# schematic.net
KiCad netlist of a schematic drawn in EAGLE
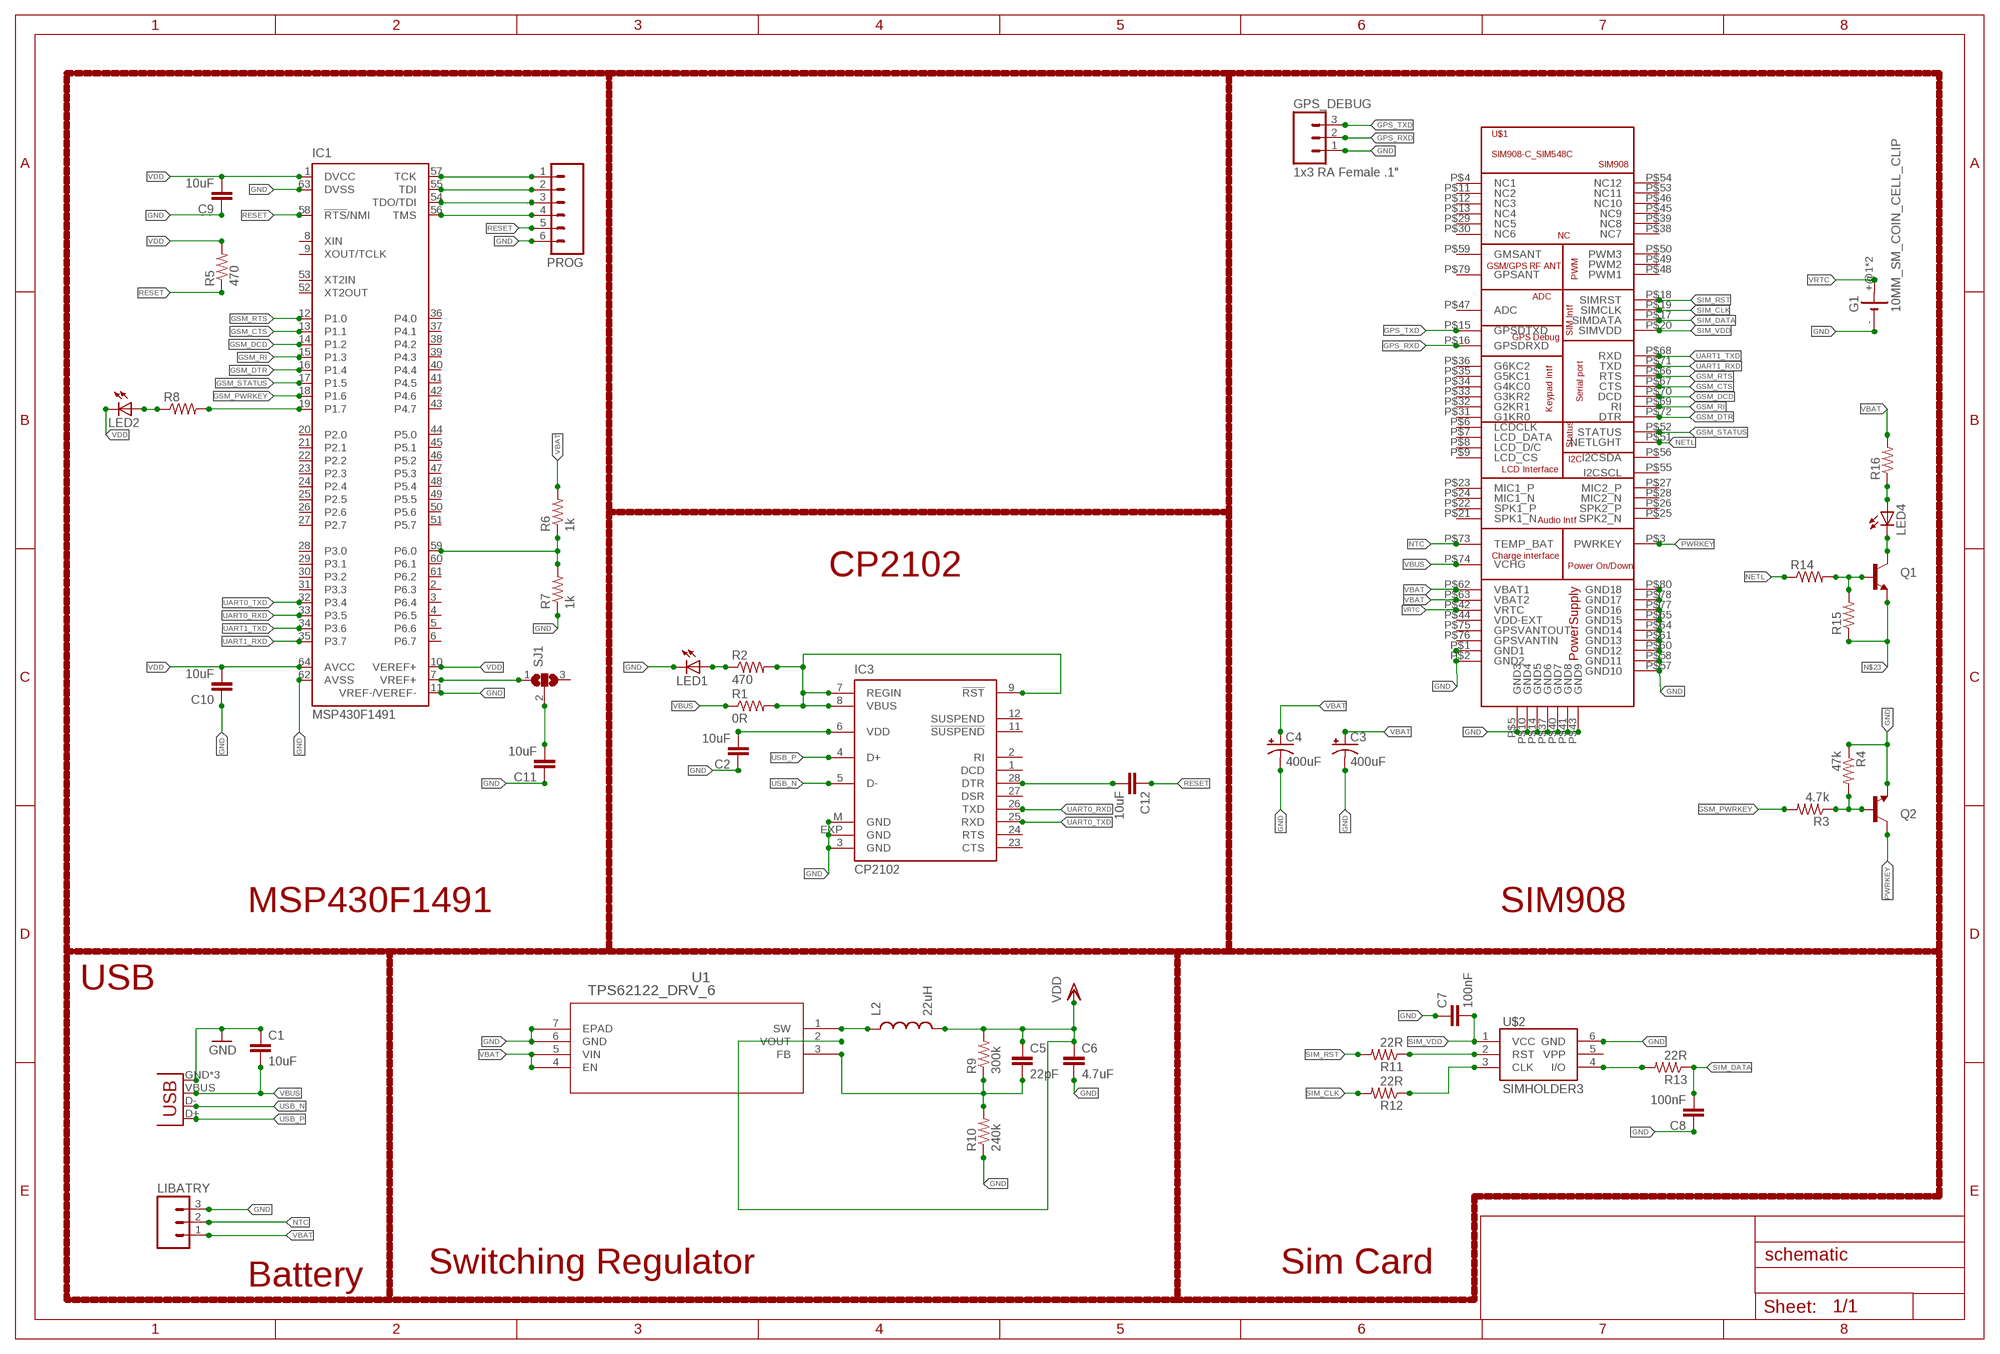
[diagram p0: schematic, sheet 1]

(export (version "E")
  (design (tool "Eeschema 10.0.6"))
  (components
    (comp (ref "C1")
      (value "10uF")
      (footprint "eagle-import:0402-CAP")
      (libsource (lib "eagle-import") (part "CAP0402-CAP"))
    )
    (comp (ref "C2")
      (value "10uF")
      (footprint "eagle-import:0402-CAP")
      (libsource (lib "eagle-import") (part "CAP0402-CAP"))
    )
    (comp (ref "C3")
      (value "400uF")
      (footprint "eagle-import:PANASONIC_G")
      (libsource (lib "eagle-import") (part "CAP_POLG"))
    )
    (comp (ref "C4")
      (value "400uF")
      (footprint "eagle-import:PANASONIC_G")
      (libsource (lib "eagle-import") (part "CAP_POLG"))
    )
    (comp (ref "C5")
      (value "22pF")
      (footprint "eagle-import:0402-CAP")
      (libsource (lib "eagle-import") (part "CAP0402-CAP"))
    )
    (comp (ref "C6")
      (value "4.7uF")
      (footprint "eagle-import:0402-CAP")
      (libsource (lib "eagle-import") (part "CAP0402-CAP"))
    )
    (comp (ref "C7")
      (value "100nF")
      (footprint "eagle-import:0402-CAP")
      (libsource (lib "eagle-import") (part "CAP0402-CAP"))
    )
    (comp (ref "C8")
      (value "100nF")
      (footprint "eagle-import:0402-CAP")
      (libsource (lib "eagle-import") (part "CAP0402-CAP"))
    )
    (comp (ref "C9")
      (value "10uF")
      (footprint "eagle-import:0402-CAP")
      (libsource (lib "eagle-import") (part "CAP0402-CAP"))
    )
    (comp (ref "C10")
      (value "10uF")
      (footprint "eagle-import:0402-CAP")
      (libsource (lib "eagle-import") (part "CAP0402-CAP"))
    )
    (comp (ref "C11")
      (value "10uF")
      (footprint "eagle-import:0402-CAP")
      (libsource (lib "eagle-import") (part "CAP0402-CAP"))
    )
    (comp (ref "C12")
      (value "10uF")
      (footprint "eagle-import:0402-CAP")
      (libsource (lib "eagle-import") (part "CAP0402-CAP"))
    )
    (comp (ref "G1")
      (value "10MM_SM_COIN_CELL_CLIP")
      (footprint "eagle-import:10MM_SM_COIN_CELL_CLIP")
      (libsource (lib "eagle-import") (part "10MM_SM_COIN_CELL_CLIP"))
    )
    (comp (ref "GPS_DEBUG")
      (value "1x3 RA Female .1\"")
      (footprint "eagle-import:1X03_SMD_RA_FEMALE")
      (libsource (lib "eagle-import") (part "M03SMD_RA_FEMALE"))
    )
    (comp (ref "IC1")
      (value "MSP430F1491")
      (footprint "eagle-import:SQFP-S-10X10-64")
      (fields (field (name "MF") "TEXAS INSTRUMENT CONNECTORS") (field (name "MPN") "MSP430F1491IPM"))
      (libsource (lib "eagle-import") (part "MSP430F1491"))
    )
    (comp (ref "IC3")
      (value "CP2102")
      (footprint "eagle-import:MLP28")
      (fields (field (name "MF") "FARNELL") (field (name "MPN") "CP2102-GM"))
      (libsource (lib "eagle-import") (part "CP2102"))
    )
    (comp (ref "JP1")
      (value "USB-MICROB")
      (footprint "eagle-import:USB-MICROB")
      (libsource (lib "eagle-import") (part "USB-MICROB"))
    )
    (comp (ref "L2")
      (value "22uH")
      (footprint "eagle-import:C0402")
      (libsource (lib "eagle-import") (part "INDUCTOR0402"))
    )
    (comp (ref "LED1")
      (value "LEDSML0603")
      (footprint "eagle-import:SML0603")
      (libsource (lib "eagle-import") (part "LEDSML0603"))
    )
    (comp (ref "LED2")
      (value "LEDSML0603")
      (footprint "eagle-import:SML0603")
      (libsource (lib "eagle-import") (part "LEDSML0603"))
    )
    (comp (ref "LED4")
      (value "LEDSML0603")
      (footprint "eagle-import:SML0603")
      (libsource (lib "eagle-import") (part "LEDSML0603"))
    )
    (comp (ref "LIBATRY")
      (value "M03PTH")
      (footprint "eagle-import:1X03")
      (libsource (lib "eagle-import") (part "M03PTH"))
    )
    (comp (ref "PROG")
      (value "M06SMD-STRAIGHT")
      (footprint "eagle-import:1X06_SMD_STRAIGHT")
      (libsource (lib "eagle-import") (part "M06SMD-STRAIGHT"))
    )
    (comp (ref "Q1")
      (value "TRANSISTOR_NPNSOT23")
      (footprint "eagle-import:SOT23")
      (libsource (lib "eagle-import") (part "TRANSISTOR_NPNSOT23"))
    )
    (comp (ref "Q2")
      (value "TRANSISTOR_NPNSOT23")
      (footprint "eagle-import:SOT23")
      (libsource (lib "eagle-import") (part "TRANSISTOR_NPNSOT23"))
    )
    (comp (ref "R1")
      (value "0R")
      (footprint "eagle-import:0402-RES")
      (libsource (lib "eagle-import") (part "SparkFun-Passives_RESISTOR0402-RES"))
    )
    (comp (ref "R2")
      (value "470")
      (footprint "eagle-import:0402-RES")
      (libsource (lib "eagle-import") (part "SparkFun-Passives_RESISTOR0402-RES"))
    )
    (comp (ref "R3")
      (value "4.7k")
      (footprint "eagle-import:0402-RES")
      (libsource (lib "eagle-import") (part "SparkFun-Passives_RESISTOR0402-RES"))
    )
    (comp (ref "R4")
      (value "47k")
      (footprint "eagle-import:0402-RES")
      (libsource (lib "eagle-import") (part "SparkFun-Passives_RESISTOR0402-RES"))
    )
    (comp (ref "R5")
      (value "470")
      (footprint "eagle-import:0402-RES")
      (libsource (lib "eagle-import") (part "SparkFun-Passives_RESISTOR0402-RES"))
    )
    (comp (ref "R6")
      (value "1k")
      (footprint "eagle-import:0402-RES")
      (libsource (lib "eagle-import") (part "SparkFun-Passives_RESISTOR0402-RES"))
    )
    (comp (ref "R7")
      (value "1k")
      (footprint "eagle-import:0402-RES")
      (libsource (lib "eagle-import") (part "SparkFun-Passives_RESISTOR0402-RES"))
    )
    (comp (ref "R8")
      (value "RESISTOR0402-RES")
      (footprint "eagle-import:0402-RES")
      (libsource (lib "eagle-import") (part "RESISTOR0402-RES"))
    )
    (comp (ref "R9")
      (value "300k")
      (footprint "eagle-import:0402-RES")
      (libsource (lib "eagle-import") (part "RESISTOR0402-RES"))
    )
    (comp (ref "R10")
      (value "240k")
      (footprint "eagle-import:0402-RES")
      (libsource (lib "eagle-import") (part "RESISTOR0402-RES"))
    )
    (comp (ref "R11")
      (value "22R")
      (footprint "eagle-import:0402-RES")
      (libsource (lib "eagle-import") (part "RESISTOR0402-RES"))
    )
    (comp (ref "R12")
      (value "22R")
      (footprint "eagle-import:0402-RES")
      (libsource (lib "eagle-import") (part "RESISTOR0402-RES"))
    )
    (comp (ref "R13")
      (value "22R")
      (footprint "eagle-import:0402-RES")
      (libsource (lib "eagle-import") (part "RESISTOR0402-RES"))
    )
    (comp (ref "R14")
      (value "RESISTOR0402-RES")
      (footprint "eagle-import:0402-RES")
      (libsource (lib "eagle-import") (part "SparkFun-Passives_RESISTOR0402-RES"))
    )
    (comp (ref "R15")
      (value "RESISTOR0402-RES")
      (footprint "eagle-import:0402-RES")
      (libsource (lib "eagle-import") (part "SparkFun-Passives_RESISTOR0402-RES"))
    )
    (comp (ref "R16")
      (value "RESISTOR0402-RES")
      (footprint "eagle-import:0402-RES")
      (libsource (lib "eagle-import") (part "RESISTOR0402-RES"))
    )
    (comp (ref "SJ1")
      (value "SJ2W")
      (footprint "eagle-import:SJ_2")
      (libsource (lib "eagle-import") (part "SJ2W"))
    )
    (comp (ref "U$1")
      (value "SIM908-C_SIM548C")
      (footprint "eagle-import:SIM908-C_SIM548C")
      (libsource (lib "eagle-import") (part "SIM908-C_SIM548C"))
    )
    (comp (ref "U$2")
      (value "SIMHOLDER3")
      (footprint "eagle-import:SIMHOLDER3")
      (libsource (lib "eagle-import") (part "SIMHOLDER3"))
    )
    (comp (ref "U1")
      (value "TPS62122_DRV_6")
      (footprint "eagle-import:DRV6_1P6X1")
      (fields
        (field (name "GENERIC_PART_NUMBER") "TPS62122")
        (field (name "MANUFACTURER") "Texas Instruments")
        (field (name "MANUFACTURER_PART_NUMBER") "tps62122_drv_6")
      )
      (libsource (lib "eagle-import") (part "TPS62122_DRV_6"))
    )
  )
  (nets
    (net (code "1") (name "GND") (class "Default")
      (node (ref "C1") (pin "1") (pinfunction "1_1") (pintype "passive"))
      (node (ref "C10") (pin "1") (pinfunction "1_1") (pintype "passive"))
      (node (ref "C11") (pin "1") (pinfunction "1_1") (pintype "passive"))
      (node (ref "C2") (pin "1") (pinfunction "1_1") (pintype "passive"))
      (node (ref "C3") (pin "-") (pinfunction "-_-") (pintype "passive"))
      (node (ref "C4") (pin "-") (pinfunction "-_-") (pintype "passive"))
      (node (ref "C6") (pin "2") (pinfunction "2_2") (pintype "passive"))
      (node (ref "C7") (pin "1") (pinfunction "1_1") (pintype "passive"))
      (node (ref "C8") (pin "1") (pinfunction "1_1") (pintype "passive"))
      (node (ref "C9") (pin "1") (pinfunction "1_1") (pintype "passive"))
      (node (ref "G1") (pin "-") (pinfunction "-_-") (pintype "passive"))
      (node (ref "GPS_DEBUG") (pin "1") (pinfunction "1_1") (pintype "passive"))
      (node (ref "IC1") (pin "11") (pinfunction "VREF-/VEREF-_11") (pintype "bidirectional"))
      (node (ref "IC1") (pin "62") (pinfunction "AVSS_62") (pintype "power_in"))
      (node (ref "IC1") (pin "63") (pinfunction "DVSS_63") (pintype "power_in"))
      (node (ref "IC3") (pin "3") (pinfunction "GND_3") (pintype "power_in"))
      (node (ref "IC3") (pin "EXP") (pinfunction "GND_EXP") (pintype "power_in"))
      (node (ref "IC3") (pin "M") (pinfunction "GND_M") (pintype "power_in"))
      (node (ref "JP1") (pin "GND") (pinfunction "GND_GND") (pintype "bidirectional"))
      (node (ref "JP1") (pin "MT1") (pinfunction "GND_MT1") (pintype "bidirectional"))
      (node (ref "JP1") (pin "MT2") (pinfunction "GND_MT2") (pintype "bidirectional"))
      (node (ref "LED1") (pin "C") (pinfunction "C_C") (pintype "passive"))
      (node (ref "LIBATRY") (pin "3") (pinfunction "3_3") (pintype "passive"))
      (node (ref "PROG") (pin "6") (pinfunction "6_6") (pintype "passive"))
      (node (ref "Q2") (pin "2") (pinfunction "E_2") (pintype "passive"))
      (node (ref "R10") (pin "1") (pinfunction "1_1") (pintype "passive"))
      (node (ref "R4") (pin "1") (pinfunction "1_1") (pintype "passive"))
      (node (ref "R7") (pin "1") (pinfunction "1_1") (pintype "passive"))
      (node (ref "U$1") (pin "P$1") (pinfunction "GND1_P$1") (pintype "bidirectional"))
      (node (ref "U$1") (pin "P$10") (pinfunction "GND4_P$10") (pintype "bidirectional"))
      (node (ref "U$1") (pin "P$14") (pinfunction "GND5_P$14") (pintype "bidirectional"))
      (node (ref "U$1") (pin "P$2") (pinfunction "GND2_P$2") (pintype "bidirectional"))
      (node (ref "U$1") (pin "P$37") (pinfunction "GND6_P$37") (pintype "bidirectional"))
      (node (ref "U$1") (pin "P$40") (pinfunction "GND7_P$40") (pintype "bidirectional"))
      (node (ref "U$1") (pin "P$41") (pinfunction "GND8_P$41") (pintype "bidirectional"))
      (node (ref "U$1") (pin "P$43") (pinfunction "GND9_P$43") (pintype "bidirectional"))
      (node (ref "U$1") (pin "P$5") (pinfunction "GND3_P$5") (pintype "bidirectional"))
      (node (ref "U$1") (pin "P$57") (pinfunction "GND10_P$57") (pintype "bidirectional"))
      (node (ref "U$1") (pin "P$58") (pinfunction "GND11_P$58") (pintype "bidirectional"))
      (node (ref "U$1") (pin "P$60") (pinfunction "GND12_P$60") (pintype "bidirectional"))
      (node (ref "U$1") (pin "P$61") (pinfunction "GND13_P$61") (pintype "bidirectional"))
      (node (ref "U$1") (pin "P$64") (pinfunction "GND14_P$64") (pintype "bidirectional"))
      (node (ref "U$1") (pin "P$65") (pinfunction "GND15_P$65") (pintype "bidirectional"))
      (node (ref "U$1") (pin "P$77") (pinfunction "GND16_P$77") (pintype "bidirectional"))
      (node (ref "U$1") (pin "P$78") (pinfunction "GND17_P$78") (pintype "bidirectional"))
      (node (ref "U$1") (pin "P$80") (pinfunction "GND18_P$80") (pintype "bidirectional"))
      (node (ref "U$2") (pin "6") (pinfunction "GND_6") (pintype "bidirectional"))
      (node (ref "U1") (pin "6") (pinfunction "GND_6") (pintype "power_in"))
      (node (ref "U1") (pin "7") (pinfunction "EPAD_7") (pintype "passive"))
    )
    (net (code "2") (name "GPS_RXD") (class "Default")
      (node (ref "GPS_DEBUG") (pin "2") (pinfunction "2_2") (pintype "passive"))
      (node (ref "U$1") (pin "P$16") (pinfunction "GPSDRXD_P$16") (pintype "bidirectional"))
    )
    (net (code "3") (name "GPS_TXD") (class "Default")
      (node (ref "GPS_DEBUG") (pin "3") (pinfunction "3_3") (pintype "passive"))
      (node (ref "U$1") (pin "P$15") (pinfunction "GPSDTXD_P$15") (pintype "bidirectional"))
    )
    (net (code "4") (name "GSM_CTS") (class "Default")
      (node (ref "IC1") (pin "13") (pinfunction "P1.1_13") (pintype "bidirectional"))
      (node (ref "U$1") (pin "P$67") (pinfunction "CTS_P$67") (pintype "bidirectional"))
    )
    (net (code "5") (name "GSM_DCD") (class "Default")
      (node (ref "IC1") (pin "14") (pinfunction "P1.2_14") (pintype "bidirectional"))
      (node (ref "U$1") (pin "P$70") (pinfunction "DCD_P$70") (pintype "bidirectional"))
    )
    (net (code "6") (name "GSM_DTR") (class "Default")
      (node (ref "IC1") (pin "16") (pinfunction "P1.4_16") (pintype "bidirectional"))
      (node (ref "U$1") (pin "P$72") (pinfunction "DTR_P$72") (pintype "bidirectional"))
    )
    (net (code "7") (name "GSM_PWRKEY") (class "Default")
      (node (ref "IC1") (pin "18") (pinfunction "P1.6_18") (pintype "bidirectional"))
      (node (ref "R3") (pin "2") (pinfunction "2_2") (pintype "passive"))
    )
    (net (code "8") (name "GSM_RI") (class "Default")
      (node (ref "IC1") (pin "15") (pinfunction "P1.3_15") (pintype "bidirectional"))
      (node (ref "U$1") (pin "P$69") (pinfunction "RI_P$69") (pintype "bidirectional"))
    )
    (net (code "9") (name "GSM_RTS") (class "Default")
      (node (ref "IC1") (pin "12") (pinfunction "P1.0_12") (pintype "bidirectional"))
      (node (ref "U$1") (pin "P$66") (pinfunction "RTS_P$66") (pintype "bidirectional"))
    )
    (net (code "10") (name "GSM_STATUS") (class "Default")
      (node (ref "IC1") (pin "17") (pinfunction "P1.5_17") (pintype "bidirectional"))
      (node (ref "U$1") (pin "P$52") (pinfunction "STATUS_P$52") (pintype "bidirectional"))
    )
    (net (code "11") (name "N$23") (class "Default")
      (node (ref "Q1") (pin "2") (pinfunction "E_2") (pintype "passive"))
      (node (ref "R15") (pin "1") (pinfunction "1_1") (pintype "passive"))
    )
    (net (code "12") (name "NETL") (class "Default")
      (node (ref "R14") (pin "1") (pinfunction "1_1") (pintype "passive"))
      (node (ref "U$1") (pin "P$51") (pinfunction "NETLGHT_P$51") (pintype "bidirectional"))
    )
    (net (code "13") (name "NTC") (class "Default")
      (node (ref "LIBATRY") (pin "2") (pinfunction "2_2") (pintype "passive"))
      (node (ref "U$1") (pin "P$73") (pinfunction "TEMP_BAT_P$73") (pintype "bidirectional"))
    )
    (net (code "14") (name "Net-(C11-Pad2)") (class "Default")
      (node (ref "C11") (pin "2") (pinfunction "2_2") (pintype "passive"))
      (node (ref "SJ1") (pin "2") (pinfunction "2_2") (pintype "passive"))
    )
    (net (code "15") (name "Net-(IC1-P1.7)") (class "Default")
      (node (ref "IC1") (pin "19") (pinfunction "P1.7_19") (pintype "bidirectional"))
      (node (ref "R8") (pin "2") (pinfunction "2_2") (pintype "passive"))
    )
    (net (code "16") (name "Net-(IC1-P6.0)") (class "Default")
      (node (ref "IC1") (pin "59") (pinfunction "P6.0_59") (pintype "bidirectional"))
      (node (ref "R6") (pin "1") (pinfunction "1_1") (pintype "passive"))
      (node (ref "R7") (pin "2") (pinfunction "2_2") (pintype "passive"))
    )
    (net (code "17") (name "Net-(IC1-TCK)") (class "Default")
      (node (ref "IC1") (pin "57") (pinfunction "TCK_57") (pintype "input"))
      (node (ref "PROG") (pin "1") (pinfunction "1_1") (pintype "passive"))
    )
    (net (code "18") (name "Net-(IC1-TDI)") (class "Default")
      (node (ref "IC1") (pin "55") (pinfunction "TDI_55") (pintype "input"))
      (node (ref "PROG") (pin "2") (pinfunction "2_2") (pintype "passive"))
    )
    (net (code "19") (name "Net-(IC1-TDO{slash}TDI)") (class "Default")
      (node (ref "IC1") (pin "54") (pinfunction "TDO/TDI_54") (pintype "bidirectional"))
      (node (ref "PROG") (pin "3") (pinfunction "3_3") (pintype "passive"))
    )
    (net (code "20") (name "Net-(IC1-TMS)") (class "Default")
      (node (ref "IC1") (pin "56") (pinfunction "TMS_56") (pintype "input"))
      (node (ref "PROG") (pin "4") (pinfunction "4_4") (pintype "passive"))
    )
    (net (code "21") (name "Net-(IC1-VREF+)") (class "Default")
      (node (ref "IC1") (pin "7") (pinfunction "VREF+_7") (pintype "output"))
      (node (ref "SJ1") (pin "1") (pinfunction "1_1") (pintype "passive"))
    )
    (net (code "22") (name "Net-(IC3-DTR)") (class "Default")
      (node (ref "C12") (pin "2") (pinfunction "2_2") (pintype "passive"))
      (node (ref "IC3") (pin "28") (pinfunction "DTR_28") (pintype "output"))
    )
    (net (code "23") (name "Net-(IC3-REGIN)") (class "Default")
      (node (ref "IC3") (pin "7") (pinfunction "REGIN_7") (pintype "passive"))
      (node (ref "IC3") (pin "8") (pinfunction "VBUS_8") (pintype "input"))
      (node (ref "IC3") (pin "9") (pinfunction "~{RST}_9") (pintype "bidirectional"))
      (node (ref "R1") (pin "2") (pinfunction "2_2") (pintype "passive"))
      (node (ref "R2") (pin "2") (pinfunction "2_2") (pintype "passive"))
    )
    (net (code "24") (name "Net-(IC3-VDD)") (class "Default")
      (node (ref "C2") (pin "2") (pinfunction "2_2") (pintype "passive"))
      (node (ref "IC3") (pin "6") (pinfunction "VDD_6") (pintype "power_in"))
    )
    (net (code "25") (name "Net-(LED1-PadA)") (class "Default")
      (node (ref "LED1") (pin "A") (pinfunction "A_A") (pintype "passive"))
      (node (ref "R2") (pin "1") (pinfunction "1_1") (pintype "passive"))
    )
    (net (code "26") (name "Net-(LED2-PadA)") (class "Default")
      (node (ref "LED2") (pin "A") (pinfunction "A_A") (pintype "passive"))
      (node (ref "R8") (pin "1") (pinfunction "1_1") (pintype "passive"))
    )
    (net (code "27") (name "Net-(LED4-PadA)") (class "Default")
      (node (ref "LED4") (pin "A") (pinfunction "A_A") (pintype "passive"))
      (node (ref "R16") (pin "1") (pinfunction "1_1") (pintype "passive"))
    )
    (net (code "28") (name "Net-(Q1-B)") (class "Default")
      (node (ref "Q1") (pin "1") (pinfunction "B_1") (pintype "passive"))
      (node (ref "R14") (pin "2") (pinfunction "2_2") (pintype "passive"))
      (node (ref "R15") (pin "2") (pinfunction "2_2") (pintype "passive"))
    )
    (net (code "29") (name "Net-(Q1-C)") (class "Default")
      (node (ref "LED4") (pin "C") (pinfunction "C_C") (pintype "passive"))
      (node (ref "Q1") (pin "3") (pinfunction "C_3") (pintype "passive"))
    )
    (net (code "30") (name "Net-(Q2-B)") (class "Default")
      (node (ref "Q2") (pin "1") (pinfunction "B_1") (pintype "passive"))
      (node (ref "R3") (pin "1") (pinfunction "1_1") (pintype "passive"))
      (node (ref "R4") (pin "2") (pinfunction "2_2") (pintype "passive"))
    )
    (net (code "31") (name "Net-(U$2-CLK)") (class "Default")
      (node (ref "R12") (pin "1") (pinfunction "1_1") (pintype "passive"))
      (node (ref "U$2") (pin "3") (pinfunction "CLK_3") (pintype "bidirectional"))
    )
    (net (code "32") (name "Net-(U$2-I{slash}O)") (class "Default")
      (node (ref "R13") (pin "2") (pinfunction "2_2") (pintype "passive"))
      (node (ref "U$2") (pin "4") (pinfunction "I/O_4") (pintype "bidirectional"))
    )
    (net (code "33") (name "Net-(U$2-RST)") (class "Default")
      (node (ref "R11") (pin "1") (pinfunction "1_1") (pintype "passive"))
      (node (ref "U$2") (pin "2") (pinfunction "RST_2") (pintype "bidirectional"))
    )
    (net (code "34") (name "Net-(U1-FB)") (class "Default")
      (node (ref "C5") (pin "2") (pinfunction "2_2") (pintype "passive"))
      (node (ref "R10") (pin "2") (pinfunction "2_2") (pintype "passive"))
      (node (ref "R9") (pin "1") (pinfunction "1_1") (pintype "passive"))
      (node (ref "U1") (pin "3") (pinfunction "FB_3") (pintype "input"))
    )
    (net (code "35") (name "Net-(U1-SW)") (class "Default")
      (node (ref "L2") (pin "1") (pinfunction "1_1") (pintype "passive"))
      (node (ref "U1") (pin "1") (pinfunction "SW_1") (pintype "output"))
    )
    (net (code "36") (name "PWRKEY") (class "Default")
      (node (ref "Q2") (pin "3") (pinfunction "C_3") (pintype "passive"))
      (node (ref "U$1") (pin "P$3") (pinfunction "PWRKEY_P$3") (pintype "bidirectional"))
    )
    (net (code "37") (name "RESET") (class "Default")
      (node (ref "C12") (pin "1") (pinfunction "1_1") (pintype "passive"))
      (node (ref "IC1") (pin "58") (pinfunction "~{RTS}/NMI_58") (pintype "input"))
      (node (ref "PROG") (pin "5") (pinfunction "5_5") (pintype "passive"))
      (node (ref "R5") (pin "1") (pinfunction "1_1") (pintype "passive"))
    )
    (net (code "38") (name "SIM_CLK") (class "Default")
      (node (ref "R12") (pin "2") (pinfunction "2_2") (pintype "passive"))
      (node (ref "U$1") (pin "P$19") (pinfunction "SIMCLK_P$19") (pintype "bidirectional"))
    )
    (net (code "39") (name "SIM_DATA") (class "Default")
      (node (ref "C8") (pin "2") (pinfunction "2_2") (pintype "passive"))
      (node (ref "R13") (pin "1") (pinfunction "1_1") (pintype "passive"))
      (node (ref "U$1") (pin "P$17") (pinfunction "SIMDATA_P$17") (pintype "bidirectional"))
    )
    (net (code "40") (name "SIM_RST") (class "Default")
      (node (ref "R11") (pin "2") (pinfunction "2_2") (pintype "passive"))
      (node (ref "U$1") (pin "P$18") (pinfunction "SIMRST_P$18") (pintype "bidirectional"))
    )
    (net (code "41") (name "SIM_VDD") (class "Default")
      (node (ref "C7") (pin "2") (pinfunction "2_2") (pintype "passive"))
      (node (ref "U$1") (pin "P$20") (pinfunction "SIMVDD_P$20") (pintype "bidirectional"))
      (node (ref "U$2") (pin "1") (pinfunction "VCC_1") (pintype "bidirectional"))
    )
    (net (code "42") (name "UART0_RXD") (class "Default")
      (node (ref "IC1") (pin "33") (pinfunction "P3.5_33") (pintype "bidirectional"))
      (node (ref "IC3") (pin "26") (pinfunction "TXD_26") (pintype "output"))
    )
    (net (code "43") (name "UART0_TXD") (class "Default")
      (node (ref "IC1") (pin "32") (pinfunction "P3.4_32") (pintype "bidirectional"))
      (node (ref "IC3") (pin "25") (pinfunction "RXD_25") (pintype "input"))
    )
    (net (code "44") (name "UART1_RXD") (class "Default")
      (node (ref "IC1") (pin "35") (pinfunction "P3.7_35") (pintype "bidirectional"))
      (node (ref "U$1") (pin "P$71") (pinfunction "TXD_P$71") (pintype "bidirectional"))
    )
    (net (code "45") (name "UART1_TXD") (class "Default")
      (node (ref "IC1") (pin "34") (pinfunction "P3.6_34") (pintype "bidirectional"))
      (node (ref "U$1") (pin "P$68") (pinfunction "RXD_P$68") (pintype "bidirectional"))
    )
    (net (code "46") (name "USB_N") (class "Default")
      (node (ref "IC3") (pin "5") (pinfunction "D-_5") (pintype "bidirectional"))
      (node (ref "JP1") (pin "D-") (pinfunction "D-_D-") (pintype "bidirectional"))
    )
    (net (code "47") (name "USB_P") (class "Default")
      (node (ref "IC3") (pin "4") (pinfunction "D+_4") (pintype "bidirectional"))
      (node (ref "JP1") (pin "D+") (pinfunction "D+_D+") (pintype "bidirectional"))
    )
    (net (code "48") (name "VBAT") (class "Default")
      (node (ref "C3") (pin "+") (pinfunction "+_+") (pintype "passive"))
      (node (ref "C4") (pin "+") (pinfunction "+_+") (pintype "passive"))
      (node (ref "LIBATRY") (pin "1") (pinfunction "1_1") (pintype "passive"))
      (node (ref "R16") (pin "2") (pinfunction "2_2") (pintype "passive"))
      (node (ref "R6") (pin "2") (pinfunction "2_2") (pintype "passive"))
      (node (ref "U$1") (pin "P$62") (pinfunction "VBAT1_P$62") (pintype "bidirectional"))
      (node (ref "U$1") (pin "P$63") (pinfunction "VBAT2_P$63") (pintype "bidirectional"))
      (node (ref "U1") (pin "4") (pinfunction "EN_4") (pintype "input"))
      (node (ref "U1") (pin "5") (pinfunction "VIN_5") (pintype "power_in"))
    )
    (net (code "49") (name "VBUS") (class "Default")
      (node (ref "C1") (pin "2") (pinfunction "2_2") (pintype "passive"))
      (node (ref "JP1") (pin "VBUS") (pinfunction "VBUS_VBUS") (pintype "bidirectional"))
      (node (ref "R1") (pin "1") (pinfunction "1_1") (pintype "passive"))
      (node (ref "U$1") (pin "P$74") (pinfunction "VCHG_P$74") (pintype "bidirectional"))
    )
    (net (code "50") (name "VDD") (class "Default")
      (node (ref "C10") (pin "2") (pinfunction "2_2") (pintype "passive"))
      (node (ref "C5") (pin "1") (pinfunction "1_1") (pintype "passive"))
      (node (ref "C6") (pin "1") (pinfunction "1_1") (pintype "passive"))
      (node (ref "C9") (pin "2") (pinfunction "2_2") (pintype "passive"))
      (node (ref "IC1") (pin "1") (pinfunction "DVCC_1") (pintype "power_in"))
      (node (ref "IC1") (pin "10") (pinfunction "VEREF+_10") (pintype "input"))
      (node (ref "IC1") (pin "64") (pinfunction "AVCC_64") (pintype "power_in"))
      (node (ref "L2") (pin "2") (pinfunction "2_2") (pintype "passive"))
      (node (ref "LED2") (pin "C") (pinfunction "C_C") (pintype "passive"))
      (node (ref "R5") (pin "2") (pinfunction "2_2") (pintype "passive"))
      (node (ref "R9") (pin "2") (pinfunction "2_2") (pintype "passive"))
      (node (ref "U1") (pin "2") (pinfunction "VOUT_2") (pintype "input"))
    )
    (net (code "51") (name "VRTC") (class "Default")
      (node (ref "G1") (pin "+@1") (pinfunction "+_+@1") (pintype "passive"))
      (node (ref "G1") (pin "+@2") (pinfunction "+_+@2") (pintype "passive"))
      (node (ref "U$1") (pin "P$42") (pinfunction "VRTC_P$42") (pintype "bidirectional"))
    )
    (net (code "52") (name "unconnected-(IC1-P2.0-Pad20)") (class "Default")
      (node (ref "IC1") (pin "20") (pinfunction "P2.0_20") (pintype "bidirectional"))
    )
    (net (code "53") (name "unconnected-(IC1-P2.1-Pad21)") (class "Default")
      (node (ref "IC1") (pin "21") (pinfunction "P2.1_21") (pintype "bidirectional"))
    )
    (net (code "54") (name "unconnected-(IC1-P2.2-Pad22)") (class "Default")
      (node (ref "IC1") (pin "22") (pinfunction "P2.2_22") (pintype "bidirectional"))
    )
    (net (code "55") (name "unconnected-(IC1-P2.3-Pad23)") (class "Default")
      (node (ref "IC1") (pin "23") (pinfunction "P2.3_23") (pintype "bidirectional"))
    )
    (net (code "56") (name "unconnected-(IC1-P2.4-Pad24)") (class "Default")
      (node (ref "IC1") (pin "24") (pinfunction "P2.4_24") (pintype "bidirectional"))
    )
    (net (code "57") (name "unconnected-(IC1-P2.5-Pad25)") (class "Default")
      (node (ref "IC1") (pin "25") (pinfunction "P2.5_25") (pintype "bidirectional"))
    )
    (net (code "58") (name "unconnected-(IC1-P2.6-Pad26)") (class "Default")
      (node (ref "IC1") (pin "26") (pinfunction "P2.6_26") (pintype "bidirectional"))
    )
    (net (code "59") (name "unconnected-(IC1-P2.7-Pad27)") (class "Default")
      (node (ref "IC1") (pin "27") (pinfunction "P2.7_27") (pintype "bidirectional"))
    )
    (net (code "60") (name "unconnected-(IC1-P3.0-Pad28)") (class "Default")
      (node (ref "IC1") (pin "28") (pinfunction "P3.0_28") (pintype "bidirectional"))
    )
    (net (code "61") (name "unconnected-(IC1-P3.1-Pad29)") (class "Default")
      (node (ref "IC1") (pin "29") (pinfunction "P3.1_29") (pintype "bidirectional"))
    )
    (net (code "62") (name "unconnected-(IC1-P3.2-Pad30)") (class "Default")
      (node (ref "IC1") (pin "30") (pinfunction "P3.2_30") (pintype "bidirectional"))
    )
    (net (code "63") (name "unconnected-(IC1-P3.3-Pad31)") (class "Default")
      (node (ref "IC1") (pin "31") (pinfunction "P3.3_31") (pintype "bidirectional"))
    )
    (net (code "64") (name "unconnected-(IC1-P4.0-Pad36)") (class "Default")
      (node (ref "IC1") (pin "36") (pinfunction "P4.0_36") (pintype "bidirectional"))
    )
    (net (code "65") (name "unconnected-(IC1-P4.1-Pad37)") (class "Default")
      (node (ref "IC1") (pin "37") (pinfunction "P4.1_37") (pintype "bidirectional"))
    )
    (net (code "66") (name "unconnected-(IC1-P4.2-Pad38)") (class "Default")
      (node (ref "IC1") (pin "38") (pinfunction "P4.2_38") (pintype "bidirectional"))
    )
    (net (code "67") (name "unconnected-(IC1-P4.3-Pad39)") (class "Default")
      (node (ref "IC1") (pin "39") (pinfunction "P4.3_39") (pintype "bidirectional"))
    )
    (net (code "68") (name "unconnected-(IC1-P4.4-Pad40)") (class "Default")
      (node (ref "IC1") (pin "40") (pinfunction "P4.4_40") (pintype "bidirectional"))
    )
    (net (code "69") (name "unconnected-(IC1-P4.5-Pad41)") (class "Default")
      (node (ref "IC1") (pin "41") (pinfunction "P4.5_41") (pintype "bidirectional"))
    )
    (net (code "70") (name "unconnected-(IC1-P4.6-Pad42)") (class "Default")
      (node (ref "IC1") (pin "42") (pinfunction "P4.6_42") (pintype "bidirectional"))
    )
    (net (code "71") (name "unconnected-(IC1-P4.7-Pad43)") (class "Default")
      (node (ref "IC1") (pin "43") (pinfunction "P4.7_43") (pintype "bidirectional"))
    )
    (net (code "72") (name "unconnected-(IC1-P5.0-Pad44)") (class "Default")
      (node (ref "IC1") (pin "44") (pinfunction "P5.0_44") (pintype "bidirectional"))
    )
    (net (code "73") (name "unconnected-(IC1-P5.1-Pad45)") (class "Default")
      (node (ref "IC1") (pin "45") (pinfunction "P5.1_45") (pintype "bidirectional"))
    )
    (net (code "74") (name "unconnected-(IC1-P5.2-Pad46)") (class "Default")
      (node (ref "IC1") (pin "46") (pinfunction "P5.2_46") (pintype "bidirectional"))
    )
    (net (code "75") (name "unconnected-(IC1-P5.3-Pad47)") (class "Default")
      (node (ref "IC1") (pin "47") (pinfunction "P5.3_47") (pintype "bidirectional"))
    )
    (net (code "76") (name "unconnected-(IC1-P5.4-Pad48)") (class "Default")
      (node (ref "IC1") (pin "48") (pinfunction "P5.4_48") (pintype "bidirectional"))
    )
    (net (code "77") (name "unconnected-(IC1-P5.5-Pad49)") (class "Default")
      (node (ref "IC1") (pin "49") (pinfunction "P5.5_49") (pintype "bidirectional"))
    )
    (net (code "78") (name "unconnected-(IC1-P5.6-Pad50)") (class "Default")
      (node (ref "IC1") (pin "50") (pinfunction "P5.6_50") (pintype "bidirectional"))
    )
    (net (code "79") (name "unconnected-(IC1-P5.7-Pad51)") (class "Default")
      (node (ref "IC1") (pin "51") (pinfunction "P5.7_51") (pintype "bidirectional"))
    )
    (net (code "80") (name "unconnected-(IC1-P6.1-Pad60)") (class "Default")
      (node (ref "IC1") (pin "60") (pinfunction "P6.1_60") (pintype "bidirectional"))
    )
    (net (code "81") (name "unconnected-(IC1-P6.2-Pad61)") (class "Default")
      (node (ref "IC1") (pin "61") (pinfunction "P6.2_61") (pintype "bidirectional"))
    )
    (net (code "82") (name "unconnected-(IC1-P6.3-Pad2)") (class "Default")
      (node (ref "IC1") (pin "2") (pinfunction "P6.3_2") (pintype "bidirectional"))
    )
    (net (code "83") (name "unconnected-(IC1-P6.4-Pad3)") (class "Default")
      (node (ref "IC1") (pin "3") (pinfunction "P6.4_3") (pintype "bidirectional"))
    )
    (net (code "84") (name "unconnected-(IC1-P6.5-Pad4)") (class "Default")
      (node (ref "IC1") (pin "4") (pinfunction "P6.5_4") (pintype "bidirectional"))
    )
    (net (code "85") (name "unconnected-(IC1-P6.6-Pad5)") (class "Default")
      (node (ref "IC1") (pin "5") (pinfunction "P6.6_5") (pintype "bidirectional"))
    )
    (net (code "86") (name "unconnected-(IC1-P6.7-Pad6)") (class "Default")
      (node (ref "IC1") (pin "6") (pinfunction "P6.7_6") (pintype "bidirectional"))
    )
    (net (code "87") (name "unconnected-(IC1-XIN-Pad8)") (class "Default")
      (node (ref "IC1") (pin "8") (pinfunction "XIN_8") (pintype "input"))
    )
    (net (code "88") (name "unconnected-(IC1-XOUT{slash}TCLK-Pad9)") (class "Default")
      (node (ref "IC1") (pin "9") (pinfunction "XOUT/TCLK_9") (pintype "bidirectional"))
    )
    (net (code "89") (name "unconnected-(IC1-XT2IN-Pad53)") (class "Default")
      (node (ref "IC1") (pin "53") (pinfunction "XT2IN_53") (pintype "input"))
    )
    (net (code "90") (name "unconnected-(IC1-XT2OUT-Pad52)") (class "Default")
      (node (ref "IC1") (pin "52") (pinfunction "XT2OUT_52") (pintype "output"))
    )
    (net (code "91") (name "unconnected-(IC3-CTS-Pad23)") (class "Default")
      (node (ref "IC3") (pin "23") (pinfunction "CTS_23") (pintype "input"))
    )
    (net (code "92") (name "unconnected-(IC3-DCD-Pad1)") (class "Default")
      (node (ref "IC3") (pin "1") (pinfunction "DCD_1") (pintype "input"))
    )
    (net (code "93") (name "unconnected-(IC3-DSR-Pad27)") (class "Default")
      (node (ref "IC3") (pin "27") (pinfunction "DSR_27") (pintype "input"))
    )
    (net (code "94") (name "unconnected-(IC3-RI-Pad2)") (class "Default")
      (node (ref "IC3") (pin "2") (pinfunction "RI_2") (pintype "input"))
    )
    (net (code "95") (name "unconnected-(IC3-RTS-Pad24)") (class "Default")
      (node (ref "IC3") (pin "24") (pinfunction "RTS_24") (pintype "output"))
    )
    (net (code "96") (name "unconnected-(IC3-SUSPEND-Pad12)") (class "Default")
      (node (ref "IC3") (pin "12") (pinfunction "SUSPEND_12") (pintype "output"))
    )
    (net (code "97") (name "unconnected-(IC3-~{SUSPEND}-Pad11)") (class "Default")
      (node (ref "IC3") (pin "11") (pinfunction "~{SUSPEND}_11") (pintype "output"))
    )
    (net (code "98") (name "unconnected-(SJ1-Pad3)") (class "Default")
      (node (ref "SJ1") (pin "3") (pinfunction "3_3") (pintype "passive"))
    )
    (net (code "99") (name "unconnected-(U$1-ADC-PadP$47)") (class "Default")
      (node (ref "U$1") (pin "P$47") (pinfunction "ADC_P$47") (pintype "bidirectional"))
    )
    (net (code "100") (name "unconnected-(U$1-G1KR0-PadP$31)") (class "Default")
      (node (ref "U$1") (pin "P$31") (pinfunction "G1KR0_P$31") (pintype "bidirectional"))
    )
    (net (code "101") (name "unconnected-(U$1-G2KR1-PadP$32)") (class "Default")
      (node (ref "U$1") (pin "P$32") (pinfunction "G2KR1_P$32") (pintype "bidirectional"))
    )
    (net (code "102") (name "unconnected-(U$1-G3KR2-PadP$33)") (class "Default")
      (node (ref "U$1") (pin "P$33") (pinfunction "G3KR2_P$33") (pintype "bidirectional"))
    )
    (net (code "103") (name "unconnected-(U$1-G4KC0-PadP$34)") (class "Default")
      (node (ref "U$1") (pin "P$34") (pinfunction "G4KC0_P$34") (pintype "bidirectional"))
    )
    (net (code "104") (name "unconnected-(U$1-G5KC1-PadP$35)") (class "Default")
      (node (ref "U$1") (pin "P$35") (pinfunction "G5KC1_P$35") (pintype "bidirectional"))
    )
    (net (code "105") (name "unconnected-(U$1-G6KC2-PadP$36)") (class "Default")
      (node (ref "U$1") (pin "P$36") (pinfunction "G6KC2_P$36") (pintype "bidirectional"))
    )
    (net (code "106") (name "unconnected-(U$1-GMSANT-PadP$59)") (class "Default")
      (node (ref "U$1") (pin "P$59") (pinfunction "GMSANT_P$59") (pintype "bidirectional"))
    )
    (net (code "107") (name "unconnected-(U$1-GPSANT-PadP$79)") (class "Default")
      (node (ref "U$1") (pin "P$79") (pinfunction "GPSANT_P$79") (pintype "bidirectional"))
    )
    (net (code "108") (name "unconnected-(U$1-GPSVANTIN-PadP$76)") (class "Default")
      (node (ref "U$1") (pin "P$76") (pinfunction "GPSVANTIN_P$76") (pintype "bidirectional"))
    )
    (net (code "109") (name "unconnected-(U$1-GPSVANTOUT-PadP$75)") (class "Default")
      (node (ref "U$1") (pin "P$75") (pinfunction "GPSVANTOUT_P$75") (pintype "bidirectional"))
    )
    (net (code "110") (name "unconnected-(U$1-I2CSCL-PadP$55)") (class "Default")
      (node (ref "U$1") (pin "P$55") (pinfunction "I2CSCL_P$55") (pintype "bidirectional"))
    )
    (net (code "111") (name "unconnected-(U$1-I2CSDA-PadP$56)") (class "Default")
      (node (ref "U$1") (pin "P$56") (pinfunction "I2CSDA_P$56") (pintype "bidirectional"))
    )
    (net (code "112") (name "unconnected-(U$1-LCDCLK-PadP$6)") (class "Default")
      (node (ref "U$1") (pin "P$6") (pinfunction "LCDCLK_P$6") (pintype "bidirectional"))
    )
    (net (code "113") (name "unconnected-(U$1-LCD_CS-PadP$9)") (class "Default")
      (node (ref "U$1") (pin "P$9") (pinfunction "LCD_CS_P$9") (pintype "bidirectional"))
    )
    (net (code "114") (name "unconnected-(U$1-LCD_DATA-PadP$7)") (class "Default")
      (node (ref "U$1") (pin "P$7") (pinfunction "LCD_DATA_P$7") (pintype "bidirectional"))
    )
    (net (code "115") (name "unconnected-(U$1-LCD_D{slash}C-PadP$8)") (class "Default")
      (node (ref "U$1") (pin "P$8") (pinfunction "LCD_D/C_P$8") (pintype "bidirectional"))
    )
    (net (code "116") (name "unconnected-(U$1-MIC1_N-PadP$24)") (class "Default")
      (node (ref "U$1") (pin "P$24") (pinfunction "MIC1_N_P$24") (pintype "bidirectional"))
    )
    (net (code "117") (name "unconnected-(U$1-MIC1_P-PadP$23)") (class "Default")
      (node (ref "U$1") (pin "P$23") (pinfunction "MIC1_P_P$23") (pintype "bidirectional"))
    )
    (net (code "118") (name "unconnected-(U$1-MIC2_N-PadP$28)") (class "Default")
      (node (ref "U$1") (pin "P$28") (pinfunction "MIC2_N_P$28") (pintype "bidirectional"))
    )
    (net (code "119") (name "unconnected-(U$1-MIC2_P-PadP$27)") (class "Default")
      (node (ref "U$1") (pin "P$27") (pinfunction "MIC2_P_P$27") (pintype "bidirectional"))
    )
    (net (code "120") (name "unconnected-(U$1-NC1-PadP$4)") (class "Default")
      (node (ref "U$1") (pin "P$4") (pinfunction "NC1_P$4") (pintype "bidirectional"))
    )
    (net (code "121") (name "unconnected-(U$1-NC2-PadP$11)") (class "Default")
      (node (ref "U$1") (pin "P$11") (pinfunction "NC2_P$11") (pintype "bidirectional"))
    )
    (net (code "122") (name "unconnected-(U$1-NC3-PadP$12)") (class "Default")
      (node (ref "U$1") (pin "P$12") (pinfunction "NC3_P$12") (pintype "bidirectional"))
    )
    (net (code "123") (name "unconnected-(U$1-NC4-PadP$13)") (class "Default")
      (node (ref "U$1") (pin "P$13") (pinfunction "NC4_P$13") (pintype "bidirectional"))
    )
    (net (code "124") (name "unconnected-(U$1-NC5-PadP$29)") (class "Default")
      (node (ref "U$1") (pin "P$29") (pinfunction "NC5_P$29") (pintype "bidirectional"))
    )
    (net (code "125") (name "unconnected-(U$1-NC6-PadP$30)") (class "Default")
      (node (ref "U$1") (pin "P$30") (pinfunction "NC6_P$30") (pintype "bidirectional"))
    )
    (net (code "126") (name "unconnected-(U$1-NC7-PadP$38)") (class "Default")
      (node (ref "U$1") (pin "P$38") (pinfunction "NC7_P$38") (pintype "bidirectional"))
    )
    (net (code "127") (name "unconnected-(U$1-NC8-PadP$39)") (class "Default")
      (node (ref "U$1") (pin "P$39") (pinfunction "NC8_P$39") (pintype "bidirectional"))
    )
    (net (code "128") (name "unconnected-(U$1-NC9-PadP$45)") (class "Default")
      (node (ref "U$1") (pin "P$45") (pinfunction "NC9_P$45") (pintype "bidirectional"))
    )
    (net (code "129") (name "unconnected-(U$1-NC10-PadP$46)") (class "Default")
      (node (ref "U$1") (pin "P$46") (pinfunction "NC10_P$46") (pintype "bidirectional"))
    )
    (net (code "130") (name "unconnected-(U$1-NC11-PadP$53)") (class "Default")
      (node (ref "U$1") (pin "P$53") (pinfunction "NC11_P$53") (pintype "bidirectional"))
    )
    (net (code "131") (name "unconnected-(U$1-NC12-PadP$54)") (class "Default")
      (node (ref "U$1") (pin "P$54") (pinfunction "NC12_P$54") (pintype "bidirectional"))
    )
    (net (code "132") (name "unconnected-(U$1-PWM1-PadP$48)") (class "Default")
      (node (ref "U$1") (pin "P$48") (pinfunction "PWM1_P$48") (pintype "bidirectional"))
    )
    (net (code "133") (name "unconnected-(U$1-PWM2-PadP$49)") (class "Default")
      (node (ref "U$1") (pin "P$49") (pinfunction "PWM2_P$49") (pintype "bidirectional"))
    )
    (net (code "134") (name "unconnected-(U$1-PWM3-PadP$50)") (class "Default")
      (node (ref "U$1") (pin "P$50") (pinfunction "PWM3_P$50") (pintype "bidirectional"))
    )
    (net (code "135") (name "unconnected-(U$1-SPK1_N-PadP$21)") (class "Default")
      (node (ref "U$1") (pin "P$21") (pinfunction "SPK1_N_P$21") (pintype "bidirectional"))
    )
    (net (code "136") (name "unconnected-(U$1-SPK1_P-PadP$22)") (class "Default")
      (node (ref "U$1") (pin "P$22") (pinfunction "SPK1_P_P$22") (pintype "bidirectional"))
    )
    (net (code "137") (name "unconnected-(U$1-SPK2_N-PadP$25)") (class "Default")
      (node (ref "U$1") (pin "P$25") (pinfunction "SPK2_N_P$25") (pintype "bidirectional"))
    )
    (net (code "138") (name "unconnected-(U$1-SPK2_P-PadP$26)") (class "Default")
      (node (ref "U$1") (pin "P$26") (pinfunction "SPK2_P_P$26") (pintype "bidirectional"))
    )
    (net (code "139") (name "unconnected-(U$1-VDD-EXT-PadP$44)") (class "Default")
      (node (ref "U$1") (pin "P$44") (pinfunction "VDD-EXT_P$44") (pintype "bidirectional"))
    )
    (net (code "140") (name "unconnected-(U$2-VPP-Pad5)") (class "Default")
      (node (ref "U$2") (pin "5") (pinfunction "VPP_5") (pintype "bidirectional"))
    )
  )
)
